# untitled.net
KiCad netlist of a schematic drawn in EAGLE
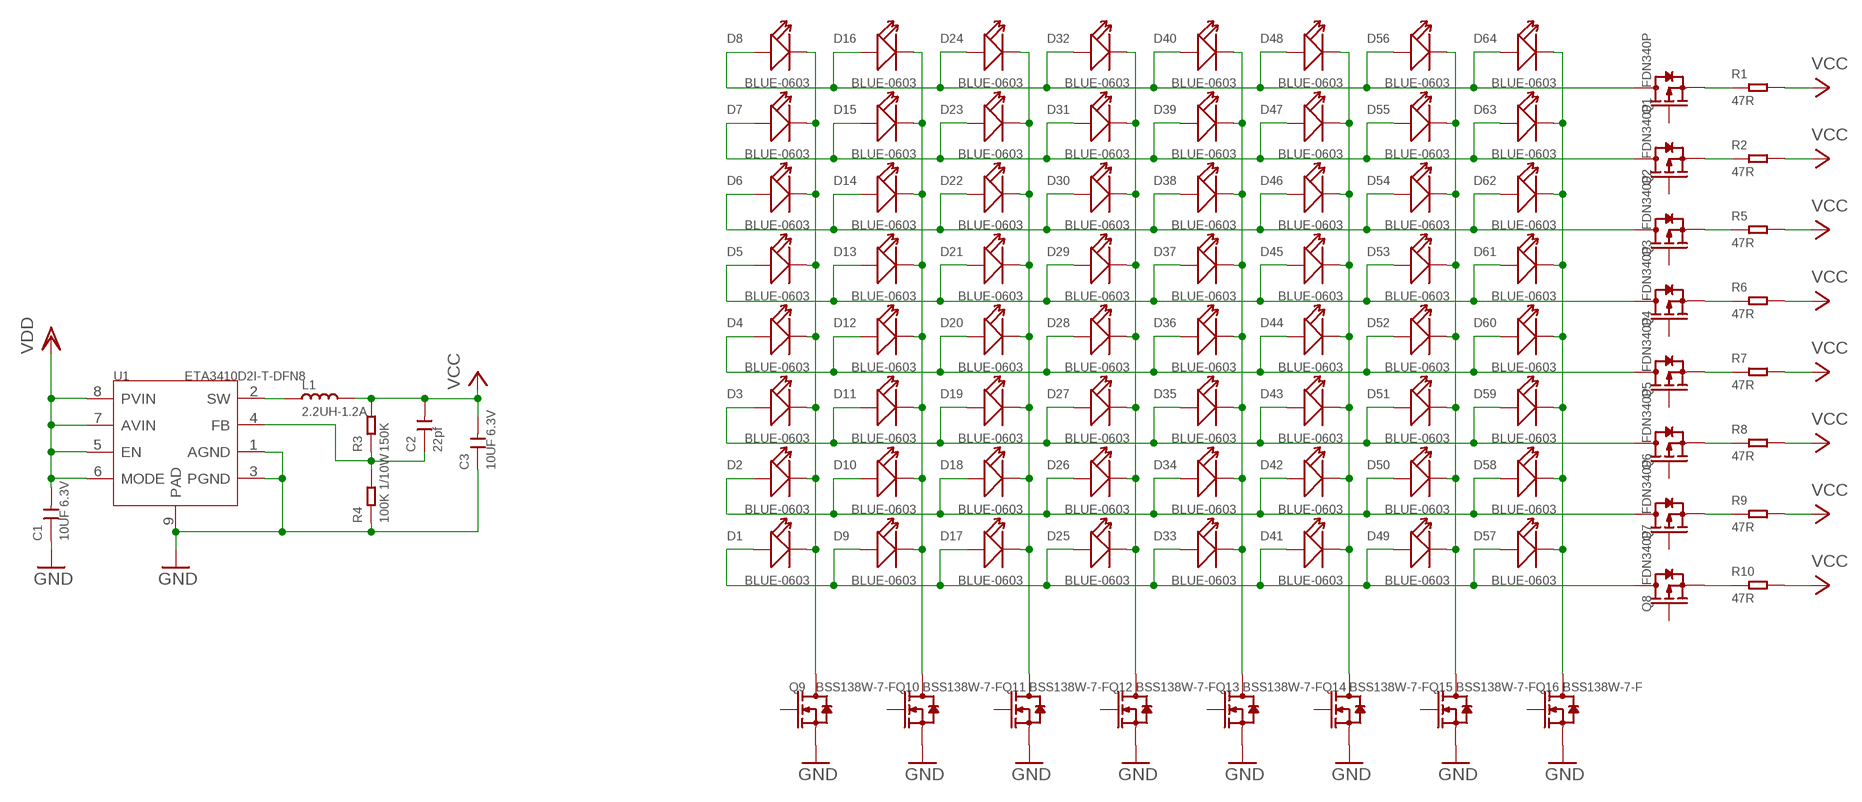
[diagram p0: schematic, sheet 1]

(export (version "E")
  (design (tool "Eeschema 10.0.6"))
  (components
    (comp (ref "C1")
      (value "10UF 6.3V")
      (footprint "eagle-import:C0603")
      (fields (field (name "MPN") "CC0603MRX5R5BB106"))
      (libsource (lib "eagle-import") (part "CERAMIC-10UF-6.3V-20%-X5R(0603)"))
    )
    (comp (ref "C2")
      (value "22pf")
      (footprint "eagle-import:C0603")
      (fields (field (name "MPN") "CC0603JRNPO9BN220"))
      (libsource (lib "eagle-import") (part "CERAMIC-22PF-50V-5%-NPO(0603)"))
    )
    (comp (ref "C3")
      (value "10UF 6.3V")
      (footprint "eagle-import:C0603")
      (fields (field (name "MPN") "CC0603MRX5R5BB106"))
      (libsource (lib "eagle-import") (part "CERAMIC-10UF-6.3V-20%-X5R(0603)"))
    )
    (comp (ref "D1")
      (value "BLUE-0603")
      (footprint "eagle-import:LED-0603")
      (fields (field (name "MPN") "19-217-BHC-ZL1M2RY-3T"))
      (libsource (lib "eagle-import") (part "SMD-LED-CLEAR-BLUE(0603)"))
    )
    (comp (ref "D2")
      (value "BLUE-0603")
      (footprint "eagle-import:LED-0603")
      (fields (field (name "MPN") "19-217-BHC-ZL1M2RY-3T"))
      (libsource (lib "eagle-import") (part "SMD-LED-CLEAR-BLUE(0603)"))
    )
    (comp (ref "D3")
      (value "BLUE-0603")
      (footprint "eagle-import:LED-0603")
      (fields (field (name "MPN") "19-217-BHC-ZL1M2RY-3T"))
      (libsource (lib "eagle-import") (part "SMD-LED-CLEAR-BLUE(0603)"))
    )
    (comp (ref "D4")
      (value "BLUE-0603")
      (footprint "eagle-import:LED-0603")
      (fields (field (name "MPN") "19-217-BHC-ZL1M2RY-3T"))
      (libsource (lib "eagle-import") (part "SMD-LED-CLEAR-BLUE(0603)"))
    )
    (comp (ref "D5")
      (value "BLUE-0603")
      (footprint "eagle-import:LED-0603")
      (fields (field (name "MPN") "19-217-BHC-ZL1M2RY-3T"))
      (libsource (lib "eagle-import") (part "SMD-LED-CLEAR-BLUE(0603)"))
    )
    (comp (ref "D6")
      (value "BLUE-0603")
      (footprint "eagle-import:LED-0603")
      (fields (field (name "MPN") "19-217-BHC-ZL1M2RY-3T"))
      (libsource (lib "eagle-import") (part "SMD-LED-CLEAR-BLUE(0603)"))
    )
    (comp (ref "D7")
      (value "BLUE-0603")
      (footprint "eagle-import:LED-0603")
      (fields (field (name "MPN") "19-217-BHC-ZL1M2RY-3T"))
      (libsource (lib "eagle-import") (part "SMD-LED-CLEAR-BLUE(0603)"))
    )
    (comp (ref "D8")
      (value "BLUE-0603")
      (footprint "eagle-import:LED-0603")
      (fields (field (name "MPN") "19-217-BHC-ZL1M2RY-3T"))
      (libsource (lib "eagle-import") (part "SMD-LED-CLEAR-BLUE(0603)"))
    )
    (comp (ref "D9")
      (value "BLUE-0603")
      (footprint "eagle-import:LED-0603")
      (fields (field (name "MPN") "19-217-BHC-ZL1M2RY-3T"))
      (libsource (lib "eagle-import") (part "SMD-LED-CLEAR-BLUE(0603)"))
    )
    (comp (ref "D10")
      (value "BLUE-0603")
      (footprint "eagle-import:LED-0603")
      (fields (field (name "MPN") "19-217-BHC-ZL1M2RY-3T"))
      (libsource (lib "eagle-import") (part "SMD-LED-CLEAR-BLUE(0603)"))
    )
    (comp (ref "D11")
      (value "BLUE-0603")
      (footprint "eagle-import:LED-0603")
      (fields (field (name "MPN") "19-217-BHC-ZL1M2RY-3T"))
      (libsource (lib "eagle-import") (part "SMD-LED-CLEAR-BLUE(0603)"))
    )
    (comp (ref "D12")
      (value "BLUE-0603")
      (footprint "eagle-import:LED-0603")
      (fields (field (name "MPN") "19-217-BHC-ZL1M2RY-3T"))
      (libsource (lib "eagle-import") (part "SMD-LED-CLEAR-BLUE(0603)"))
    )
    (comp (ref "D13")
      (value "BLUE-0603")
      (footprint "eagle-import:LED-0603")
      (fields (field (name "MPN") "19-217-BHC-ZL1M2RY-3T"))
      (libsource (lib "eagle-import") (part "SMD-LED-CLEAR-BLUE(0603)"))
    )
    (comp (ref "D14")
      (value "BLUE-0603")
      (footprint "eagle-import:LED-0603")
      (fields (field (name "MPN") "19-217-BHC-ZL1M2RY-3T"))
      (libsource (lib "eagle-import") (part "SMD-LED-CLEAR-BLUE(0603)"))
    )
    (comp (ref "D15")
      (value "BLUE-0603")
      (footprint "eagle-import:LED-0603")
      (fields (field (name "MPN") "19-217-BHC-ZL1M2RY-3T"))
      (libsource (lib "eagle-import") (part "SMD-LED-CLEAR-BLUE(0603)"))
    )
    (comp (ref "D16")
      (value "BLUE-0603")
      (footprint "eagle-import:LED-0603")
      (fields (field (name "MPN") "19-217-BHC-ZL1M2RY-3T"))
      (libsource (lib "eagle-import") (part "SMD-LED-CLEAR-BLUE(0603)"))
    )
    (comp (ref "D17")
      (value "BLUE-0603")
      (footprint "eagle-import:LED-0603")
      (fields (field (name "MPN") "19-217-BHC-ZL1M2RY-3T"))
      (libsource (lib "eagle-import") (part "SMD-LED-CLEAR-BLUE(0603)"))
    )
    (comp (ref "D18")
      (value "BLUE-0603")
      (footprint "eagle-import:LED-0603")
      (fields (field (name "MPN") "19-217-BHC-ZL1M2RY-3T"))
      (libsource (lib "eagle-import") (part "SMD-LED-CLEAR-BLUE(0603)"))
    )
    (comp (ref "D19")
      (value "BLUE-0603")
      (footprint "eagle-import:LED-0603")
      (fields (field (name "MPN") "19-217-BHC-ZL1M2RY-3T"))
      (libsource (lib "eagle-import") (part "SMD-LED-CLEAR-BLUE(0603)"))
    )
    (comp (ref "D20")
      (value "BLUE-0603")
      (footprint "eagle-import:LED-0603")
      (fields (field (name "MPN") "19-217-BHC-ZL1M2RY-3T"))
      (libsource (lib "eagle-import") (part "SMD-LED-CLEAR-BLUE(0603)"))
    )
    (comp (ref "D21")
      (value "BLUE-0603")
      (footprint "eagle-import:LED-0603")
      (fields (field (name "MPN") "19-217-BHC-ZL1M2RY-3T"))
      (libsource (lib "eagle-import") (part "SMD-LED-CLEAR-BLUE(0603)"))
    )
    (comp (ref "D22")
      (value "BLUE-0603")
      (footprint "eagle-import:LED-0603")
      (fields (field (name "MPN") "19-217-BHC-ZL1M2RY-3T"))
      (libsource (lib "eagle-import") (part "SMD-LED-CLEAR-BLUE(0603)"))
    )
    (comp (ref "D23")
      (value "BLUE-0603")
      (footprint "eagle-import:LED-0603")
      (fields (field (name "MPN") "19-217-BHC-ZL1M2RY-3T"))
      (libsource (lib "eagle-import") (part "SMD-LED-CLEAR-BLUE(0603)"))
    )
    (comp (ref "D24")
      (value "BLUE-0603")
      (footprint "eagle-import:LED-0603")
      (fields (field (name "MPN") "19-217-BHC-ZL1M2RY-3T"))
      (libsource (lib "eagle-import") (part "SMD-LED-CLEAR-BLUE(0603)"))
    )
    (comp (ref "D25")
      (value "BLUE-0603")
      (footprint "eagle-import:LED-0603")
      (fields (field (name "MPN") "19-217-BHC-ZL1M2RY-3T"))
      (libsource (lib "eagle-import") (part "SMD-LED-CLEAR-BLUE(0603)"))
    )
    (comp (ref "D26")
      (value "BLUE-0603")
      (footprint "eagle-import:LED-0603")
      (fields (field (name "MPN") "19-217-BHC-ZL1M2RY-3T"))
      (libsource (lib "eagle-import") (part "SMD-LED-CLEAR-BLUE(0603)"))
    )
    (comp (ref "D27")
      (value "BLUE-0603")
      (footprint "eagle-import:LED-0603")
      (fields (field (name "MPN") "19-217-BHC-ZL1M2RY-3T"))
      (libsource (lib "eagle-import") (part "SMD-LED-CLEAR-BLUE(0603)"))
    )
    (comp (ref "D28")
      (value "BLUE-0603")
      (footprint "eagle-import:LED-0603")
      (fields (field (name "MPN") "19-217-BHC-ZL1M2RY-3T"))
      (libsource (lib "eagle-import") (part "SMD-LED-CLEAR-BLUE(0603)"))
    )
    (comp (ref "D29")
      (value "BLUE-0603")
      (footprint "eagle-import:LED-0603")
      (fields (field (name "MPN") "19-217-BHC-ZL1M2RY-3T"))
      (libsource (lib "eagle-import") (part "SMD-LED-CLEAR-BLUE(0603)"))
    )
    (comp (ref "D30")
      (value "BLUE-0603")
      (footprint "eagle-import:LED-0603")
      (fields (field (name "MPN") "19-217-BHC-ZL1M2RY-3T"))
      (libsource (lib "eagle-import") (part "SMD-LED-CLEAR-BLUE(0603)"))
    )
    (comp (ref "D31")
      (value "BLUE-0603")
      (footprint "eagle-import:LED-0603")
      (fields (field (name "MPN") "19-217-BHC-ZL1M2RY-3T"))
      (libsource (lib "eagle-import") (part "SMD-LED-CLEAR-BLUE(0603)"))
    )
    (comp (ref "D32")
      (value "BLUE-0603")
      (footprint "eagle-import:LED-0603")
      (fields (field (name "MPN") "19-217-BHC-ZL1M2RY-3T"))
      (libsource (lib "eagle-import") (part "SMD-LED-CLEAR-BLUE(0603)"))
    )
    (comp (ref "D33")
      (value "BLUE-0603")
      (footprint "eagle-import:LED-0603")
      (fields (field (name "MPN") "19-217-BHC-ZL1M2RY-3T"))
      (libsource (lib "eagle-import") (part "SMD-LED-CLEAR-BLUE(0603)"))
    )
    (comp (ref "D34")
      (value "BLUE-0603")
      (footprint "eagle-import:LED-0603")
      (fields (field (name "MPN") "19-217-BHC-ZL1M2RY-3T"))
      (libsource (lib "eagle-import") (part "SMD-LED-CLEAR-BLUE(0603)"))
    )
    (comp (ref "D35")
      (value "BLUE-0603")
      (footprint "eagle-import:LED-0603")
      (fields (field (name "MPN") "19-217-BHC-ZL1M2RY-3T"))
      (libsource (lib "eagle-import") (part "SMD-LED-CLEAR-BLUE(0603)"))
    )
    (comp (ref "D36")
      (value "BLUE-0603")
      (footprint "eagle-import:LED-0603")
      (fields (field (name "MPN") "19-217-BHC-ZL1M2RY-3T"))
      (libsource (lib "eagle-import") (part "SMD-LED-CLEAR-BLUE(0603)"))
    )
    (comp (ref "D37")
      (value "BLUE-0603")
      (footprint "eagle-import:LED-0603")
      (fields (field (name "MPN") "19-217-BHC-ZL1M2RY-3T"))
      (libsource (lib "eagle-import") (part "SMD-LED-CLEAR-BLUE(0603)"))
    )
    (comp (ref "D38")
      (value "BLUE-0603")
      (footprint "eagle-import:LED-0603")
      (fields (field (name "MPN") "19-217-BHC-ZL1M2RY-3T"))
      (libsource (lib "eagle-import") (part "SMD-LED-CLEAR-BLUE(0603)"))
    )
    (comp (ref "D39")
      (value "BLUE-0603")
      (footprint "eagle-import:LED-0603")
      (fields (field (name "MPN") "19-217-BHC-ZL1M2RY-3T"))
      (libsource (lib "eagle-import") (part "SMD-LED-CLEAR-BLUE(0603)"))
    )
    (comp (ref "D40")
      (value "BLUE-0603")
      (footprint "eagle-import:LED-0603")
      (fields (field (name "MPN") "19-217-BHC-ZL1M2RY-3T"))
      (libsource (lib "eagle-import") (part "SMD-LED-CLEAR-BLUE(0603)"))
    )
    (comp (ref "D41")
      (value "BLUE-0603")
      (footprint "eagle-import:LED-0603")
      (fields (field (name "MPN") "19-217-BHC-ZL1M2RY-3T"))
      (libsource (lib "eagle-import") (part "SMD-LED-CLEAR-BLUE(0603)"))
    )
    (comp (ref "D42")
      (value "BLUE-0603")
      (footprint "eagle-import:LED-0603")
      (fields (field (name "MPN") "19-217-BHC-ZL1M2RY-3T"))
      (libsource (lib "eagle-import") (part "SMD-LED-CLEAR-BLUE(0603)"))
    )
    (comp (ref "D43")
      (value "BLUE-0603")
      (footprint "eagle-import:LED-0603")
      (fields (field (name "MPN") "19-217-BHC-ZL1M2RY-3T"))
      (libsource (lib "eagle-import") (part "SMD-LED-CLEAR-BLUE(0603)"))
    )
    (comp (ref "D44")
      (value "BLUE-0603")
      (footprint "eagle-import:LED-0603")
      (fields (field (name "MPN") "19-217-BHC-ZL1M2RY-3T"))
      (libsource (lib "eagle-import") (part "SMD-LED-CLEAR-BLUE(0603)"))
    )
    (comp (ref "D45")
      (value "BLUE-0603")
      (footprint "eagle-import:LED-0603")
      (fields (field (name "MPN") "19-217-BHC-ZL1M2RY-3T"))
      (libsource (lib "eagle-import") (part "SMD-LED-CLEAR-BLUE(0603)"))
    )
    (comp (ref "D46")
      (value "BLUE-0603")
      (footprint "eagle-import:LED-0603")
      (fields (field (name "MPN") "19-217-BHC-ZL1M2RY-3T"))
      (libsource (lib "eagle-import") (part "SMD-LED-CLEAR-BLUE(0603)"))
    )
    (comp (ref "D47")
      (value "BLUE-0603")
      (footprint "eagle-import:LED-0603")
      (fields (field (name "MPN") "19-217-BHC-ZL1M2RY-3T"))
      (libsource (lib "eagle-import") (part "SMD-LED-CLEAR-BLUE(0603)"))
    )
    (comp (ref "D48")
      (value "BLUE-0603")
      (footprint "eagle-import:LED-0603")
      (fields (field (name "MPN") "19-217-BHC-ZL1M2RY-3T"))
      (libsource (lib "eagle-import") (part "SMD-LED-CLEAR-BLUE(0603)"))
    )
    (comp (ref "D49")
      (value "BLUE-0603")
      (footprint "eagle-import:LED-0603")
      (fields (field (name "MPN") "19-217-BHC-ZL1M2RY-3T"))
      (libsource (lib "eagle-import") (part "SMD-LED-CLEAR-BLUE(0603)"))
    )
    (comp (ref "D50")
      (value "BLUE-0603")
      (footprint "eagle-import:LED-0603")
      (fields (field (name "MPN") "19-217-BHC-ZL1M2RY-3T"))
      (libsource (lib "eagle-import") (part "SMD-LED-CLEAR-BLUE(0603)"))
    )
    (comp (ref "D51")
      (value "BLUE-0603")
      (footprint "eagle-import:LED-0603")
      (fields (field (name "MPN") "19-217-BHC-ZL1M2RY-3T"))
      (libsource (lib "eagle-import") (part "SMD-LED-CLEAR-BLUE(0603)"))
    )
    (comp (ref "D52")
      (value "BLUE-0603")
      (footprint "eagle-import:LED-0603")
      (fields (field (name "MPN") "19-217-BHC-ZL1M2RY-3T"))
      (libsource (lib "eagle-import") (part "SMD-LED-CLEAR-BLUE(0603)"))
    )
    (comp (ref "D53")
      (value "BLUE-0603")
      (footprint "eagle-import:LED-0603")
      (fields (field (name "MPN") "19-217-BHC-ZL1M2RY-3T"))
      (libsource (lib "eagle-import") (part "SMD-LED-CLEAR-BLUE(0603)"))
    )
    (comp (ref "D54")
      (value "BLUE-0603")
      (footprint "eagle-import:LED-0603")
      (fields (field (name "MPN") "19-217-BHC-ZL1M2RY-3T"))
      (libsource (lib "eagle-import") (part "SMD-LED-CLEAR-BLUE(0603)"))
    )
    (comp (ref "D55")
      (value "BLUE-0603")
      (footprint "eagle-import:LED-0603")
      (fields (field (name "MPN") "19-217-BHC-ZL1M2RY-3T"))
      (libsource (lib "eagle-import") (part "SMD-LED-CLEAR-BLUE(0603)"))
    )
    (comp (ref "D56")
      (value "BLUE-0603")
      (footprint "eagle-import:LED-0603")
      (fields (field (name "MPN") "19-217-BHC-ZL1M2RY-3T"))
      (libsource (lib "eagle-import") (part "SMD-LED-CLEAR-BLUE(0603)"))
    )
    (comp (ref "D57")
      (value "BLUE-0603")
      (footprint "eagle-import:LED-0603")
      (fields (field (name "MPN") "19-217-BHC-ZL1M2RY-3T"))
      (libsource (lib "eagle-import") (part "SMD-LED-CLEAR-BLUE(0603)"))
    )
    (comp (ref "D58")
      (value "BLUE-0603")
      (footprint "eagle-import:LED-0603")
      (fields (field (name "MPN") "19-217-BHC-ZL1M2RY-3T"))
      (libsource (lib "eagle-import") (part "SMD-LED-CLEAR-BLUE(0603)"))
    )
    (comp (ref "D59")
      (value "BLUE-0603")
      (footprint "eagle-import:LED-0603")
      (fields (field (name "MPN") "19-217-BHC-ZL1M2RY-3T"))
      (libsource (lib "eagle-import") (part "SMD-LED-CLEAR-BLUE(0603)"))
    )
    (comp (ref "D60")
      (value "BLUE-0603")
      (footprint "eagle-import:LED-0603")
      (fields (field (name "MPN") "19-217-BHC-ZL1M2RY-3T"))
      (libsource (lib "eagle-import") (part "SMD-LED-CLEAR-BLUE(0603)"))
    )
    (comp (ref "D61")
      (value "BLUE-0603")
      (footprint "eagle-import:LED-0603")
      (fields (field (name "MPN") "19-217-BHC-ZL1M2RY-3T"))
      (libsource (lib "eagle-import") (part "SMD-LED-CLEAR-BLUE(0603)"))
    )
    (comp (ref "D62")
      (value "BLUE-0603")
      (footprint "eagle-import:LED-0603")
      (fields (field (name "MPN") "19-217-BHC-ZL1M2RY-3T"))
      (libsource (lib "eagle-import") (part "SMD-LED-CLEAR-BLUE(0603)"))
    )
    (comp (ref "D63")
      (value "BLUE-0603")
      (footprint "eagle-import:LED-0603")
      (fields (field (name "MPN") "19-217-BHC-ZL1M2RY-3T"))
      (libsource (lib "eagle-import") (part "SMD-LED-CLEAR-BLUE(0603)"))
    )
    (comp (ref "D64")
      (value "BLUE-0603")
      (footprint "eagle-import:LED-0603")
      (fields (field (name "MPN") "19-217-BHC-ZL1M2RY-3T"))
      (libsource (lib "eagle-import") (part "SMD-LED-CLEAR-BLUE(0603)"))
    )
    (comp (ref "L1")
      (value "2.2UH-1.2A")
      (footprint "eagle-import:L0805")
      (fields (field (name "MPN") "LQM2MPN2R2MG0"))
      (libsource (lib "eagle-import") (part "SMD-INDUCTOR-2.2UH-20%-1.2A(0805)"))
    )
    (comp (ref "Q1")
      (value "FDN340P")
      (footprint "eagle-import:SOT-23")
      (libsource (lib "eagle-import") (part "SMD-MOSFET-P-CH-20V-2A-FDN340P(SOT-23)"))
    )
    (comp (ref "Q2")
      (value "FDN340P")
      (footprint "eagle-import:SOT-23")
      (libsource (lib "eagle-import") (part "SMD-MOSFET-P-CH-20V-2A-FDN340P(SOT-23)"))
    )
    (comp (ref "Q3")
      (value "FDN340P")
      (footprint "eagle-import:SOT-23")
      (libsource (lib "eagle-import") (part "SMD-MOSFET-P-CH-20V-2A-FDN340P(SOT-23)"))
    )
    (comp (ref "Q4")
      (value "FDN340P")
      (footprint "eagle-import:SOT-23")
      (libsource (lib "eagle-import") (part "SMD-MOSFET-P-CH-20V-2A-FDN340P(SOT-23)"))
    )
    (comp (ref "Q5")
      (value "FDN340P")
      (footprint "eagle-import:SOT-23")
      (libsource (lib "eagle-import") (part "SMD-MOSFET-P-CH-20V-2A-FDN340P(SOT-23)"))
    )
    (comp (ref "Q6")
      (value "FDN340P")
      (footprint "eagle-import:SOT-23")
      (libsource (lib "eagle-import") (part "SMD-MOSFET-P-CH-20V-2A-FDN340P(SOT-23)"))
    )
    (comp (ref "Q7")
      (value "FDN340P")
      (footprint "eagle-import:SOT-23")
      (libsource (lib "eagle-import") (part "SMD-MOSFET-P-CH-20V-2A-FDN340P(SOT-23)"))
    )
    (comp (ref "Q8")
      (value "FDN340P")
      (footprint "eagle-import:SOT-23")
      (libsource (lib "eagle-import") (part "SMD-MOSFET-P-CH-20V-2A-FDN340P(SOT-23)"))
    )
    (comp (ref "Q9")
      (value "BSS138W-7-F")
      (footprint "eagle-import:SOT-23")
      (libsource (lib "eagle-import") (part "SMD-MOSFET-N-CH-50V-200MA-BSS138W-7-F(SOT-23)"))
    )
    (comp (ref "Q10")
      (value "BSS138W-7-F")
      (footprint "eagle-import:SOT-23")
      (libsource (lib "eagle-import") (part "SMD-MOSFET-N-CH-50V-200MA-BSS138W-7-F(SOT-23)"))
    )
    (comp (ref "Q11")
      (value "BSS138W-7-F")
      (footprint "eagle-import:SOT-23")
      (libsource (lib "eagle-import") (part "SMD-MOSFET-N-CH-50V-200MA-BSS138W-7-F(SOT-23)"))
    )
    (comp (ref "Q12")
      (value "BSS138W-7-F")
      (footprint "eagle-import:SOT-23")
      (libsource (lib "eagle-import") (part "SMD-MOSFET-N-CH-50V-200MA-BSS138W-7-F(SOT-23)"))
    )
    (comp (ref "Q13")
      (value "BSS138W-7-F")
      (footprint "eagle-import:SOT-23")
      (libsource (lib "eagle-import") (part "SMD-MOSFET-N-CH-50V-200MA-BSS138W-7-F(SOT-23)"))
    )
    (comp (ref "Q14")
      (value "BSS138W-7-F")
      (footprint "eagle-import:SOT-23")
      (libsource (lib "eagle-import") (part "SMD-MOSFET-N-CH-50V-200MA-BSS138W-7-F(SOT-23)"))
    )
    (comp (ref "Q15")
      (value "BSS138W-7-F")
      (footprint "eagle-import:SOT-23")
      (libsource (lib "eagle-import") (part "SMD-MOSFET-N-CH-50V-200MA-BSS138W-7-F(SOT-23)"))
    )
    (comp (ref "Q16")
      (value "BSS138W-7-F")
      (footprint "eagle-import:SOT-23")
      (libsource (lib "eagle-import") (part "SMD-MOSFET-N-CH-50V-200MA-BSS138W-7-F(SOT-23)"))
    )
    (comp (ref "R1")
      (value "47R")
      (footprint "eagle-import:PR-D2.3XL6.5MM")
      (fields (field (name "MPN") "FHCFR-1/4W-470J"))
      (libsource (lib "eagle-import") (part "DIP-RES-47R-5%-1/4W(PR-D2.3XL6.5MM)"))
    )
    (comp (ref "R2")
      (value "47R")
      (footprint "eagle-import:PR-D2.3XL6.5MM")
      (fields (field (name "MPN") "FHCFR-1/4W-470J"))
      (libsource (lib "eagle-import") (part "DIP-RES-47R-5%-1/4W(PR-D2.3XL6.5MM)"))
    )
    (comp (ref "R3")
      (value "150K")
      (footprint "eagle-import:R0603")
      (fields (field (name "MPN") "RC0603FR-07150KL"))
      (libsource (lib "eagle-import") (part "SMD-RES-150K-1%-1/10W(0603)"))
    )
    (comp (ref "R4")
      (value "100K 1/10W")
      (footprint "eagle-import:R0603")
      (fields (field (name "MPN") "RC0603JR-07100KL"))
      (libsource (lib "eagle-import") (part "SMD-RES-100K-5%-1/10W(0603)"))
    )
    (comp (ref "R5")
      (value "47R")
      (footprint "eagle-import:PR-D2.3XL6.5MM")
      (fields (field (name "MPN") "FHCFR-1/4W-470J"))
      (libsource (lib "eagle-import") (part "DIP-RES-47R-5%-1/4W(PR-D2.3XL6.5MM)"))
    )
    (comp (ref "R6")
      (value "47R")
      (footprint "eagle-import:PR-D2.3XL6.5MM")
      (fields (field (name "MPN") "FHCFR-1/4W-470J"))
      (libsource (lib "eagle-import") (part "DIP-RES-47R-5%-1/4W(PR-D2.3XL6.5MM)"))
    )
    (comp (ref "R7")
      (value "47R")
      (footprint "eagle-import:PR-D2.3XL6.5MM")
      (fields (field (name "MPN") "FHCFR-1/4W-470J"))
      (libsource (lib "eagle-import") (part "DIP-RES-47R-5%-1/4W(PR-D2.3XL6.5MM)"))
    )
    (comp (ref "R8")
      (value "47R")
      (footprint "eagle-import:PR-D2.3XL6.5MM")
      (fields (field (name "MPN") "FHCFR-1/4W-470J"))
      (libsource (lib "eagle-import") (part "DIP-RES-47R-5%-1/4W(PR-D2.3XL6.5MM)"))
    )
    (comp (ref "R9")
      (value "47R")
      (footprint "eagle-import:PR-D2.3XL6.5MM")
      (fields (field (name "MPN") "FHCFR-1/4W-470J"))
      (libsource (lib "eagle-import") (part "DIP-RES-47R-5%-1/4W(PR-D2.3XL6.5MM)"))
    )
    (comp (ref "R10")
      (value "47R")
      (footprint "eagle-import:PR-D2.3XL6.5MM")
      (fields (field (name "MPN") "FHCFR-1/4W-470J"))
      (libsource (lib "eagle-import") (part "DIP-RES-47R-5%-1/4W(PR-D2.3XL6.5MM)"))
    )
    (comp (ref "U1")
      (value "ETA3410D2I-T-DFN8")
      (footprint "eagle-import:DFN8G-0.5-2X2MM")
      (fields (field (name "MPN") "ETA3410D2I-T"))
      (libsource (lib "eagle-import") (part "PMIC-ETA3410D2I-T(DFN8-2X2)"))
    )
  )
  (nets
    (net (code "1") (name "GND") (class "Default")
      (node (ref "C1") (pin "1") (pinfunction "1_1") (pintype "passive"))
      (node (ref "C3") (pin "1") (pinfunction "1_1") (pintype "passive"))
      (node (ref "Q10") (pin "2") (pinfunction "S_2") (pintype "passive"))
      (node (ref "Q11") (pin "2") (pinfunction "S_2") (pintype "passive"))
      (node (ref "Q12") (pin "2") (pinfunction "S_2") (pintype "passive"))
      (node (ref "Q13") (pin "2") (pinfunction "S_2") (pintype "passive"))
      (node (ref "Q14") (pin "2") (pinfunction "S_2") (pintype "passive"))
      (node (ref "Q15") (pin "2") (pinfunction "S_2") (pintype "passive"))
      (node (ref "Q16") (pin "2") (pinfunction "S_2") (pintype "passive"))
      (node (ref "Q9") (pin "2") (pinfunction "S_2") (pintype "passive"))
      (node (ref "R4") (pin "1") (pinfunction "1_1") (pintype "passive"))
      (node (ref "U1") (pin "1") (pinfunction "AGND_1") (pintype "bidirectional"))
      (node (ref "U1") (pin "3") (pinfunction "PGND_3") (pintype "bidirectional"))
      (node (ref "U1") (pin "9") (pinfunction "PAD_9") (pintype "bidirectional"))
    )
    (net (code "2") (name "Net-(Q1-D)") (class "Default")
      (node (ref "D16") (pin "+") (pinfunction "+_+") (pintype "passive"))
      (node (ref "D24") (pin "+") (pinfunction "+_+") (pintype "passive"))
      (node (ref "D32") (pin "+") (pinfunction "+_+") (pintype "passive"))
      (node (ref "D40") (pin "+") (pinfunction "+_+") (pintype "passive"))
      (node (ref "D48") (pin "+") (pinfunction "+_+") (pintype "passive"))
      (node (ref "D56") (pin "+") (pinfunction "+_+") (pintype "passive"))
      (node (ref "D64") (pin "+") (pinfunction "+_+") (pintype "passive"))
      (node (ref "D8") (pin "+") (pinfunction "+_+") (pintype "passive"))
      (node (ref "Q1") (pin "3") (pinfunction "D_3") (pintype "passive"))
    )
    (net (code "3") (name "Net-(Q1-S)") (class "Default")
      (node (ref "Q1") (pin "2") (pinfunction "S_2") (pintype "passive"))
      (node (ref "R1") (pin "1") (pinfunction "1_1") (pintype "passive"))
    )
    (net (code "4") (name "Net-(Q2-D)") (class "Default")
      (node (ref "D15") (pin "+") (pinfunction "+_+") (pintype "passive"))
      (node (ref "D23") (pin "+") (pinfunction "+_+") (pintype "passive"))
      (node (ref "D31") (pin "+") (pinfunction "+_+") (pintype "passive"))
      (node (ref "D39") (pin "+") (pinfunction "+_+") (pintype "passive"))
      (node (ref "D47") (pin "+") (pinfunction "+_+") (pintype "passive"))
      (node (ref "D55") (pin "+") (pinfunction "+_+") (pintype "passive"))
      (node (ref "D63") (pin "+") (pinfunction "+_+") (pintype "passive"))
      (node (ref "D7") (pin "+") (pinfunction "+_+") (pintype "passive"))
      (node (ref "Q2") (pin "3") (pinfunction "D_3") (pintype "passive"))
    )
    (net (code "5") (name "Net-(Q2-S)") (class "Default")
      (node (ref "Q2") (pin "2") (pinfunction "S_2") (pintype "passive"))
      (node (ref "R2") (pin "1") (pinfunction "1_1") (pintype "passive"))
    )
    (net (code "6") (name "Net-(Q3-D)") (class "Default")
      (node (ref "D14") (pin "+") (pinfunction "+_+") (pintype "passive"))
      (node (ref "D22") (pin "+") (pinfunction "+_+") (pintype "passive"))
      (node (ref "D30") (pin "+") (pinfunction "+_+") (pintype "passive"))
      (node (ref "D38") (pin "+") (pinfunction "+_+") (pintype "passive"))
      (node (ref "D46") (pin "+") (pinfunction "+_+") (pintype "passive"))
      (node (ref "D54") (pin "+") (pinfunction "+_+") (pintype "passive"))
      (node (ref "D6") (pin "+") (pinfunction "+_+") (pintype "passive"))
      (node (ref "D62") (pin "+") (pinfunction "+_+") (pintype "passive"))
      (node (ref "Q3") (pin "3") (pinfunction "D_3") (pintype "passive"))
    )
    (net (code "7") (name "Net-(Q3-S)") (class "Default")
      (node (ref "Q3") (pin "2") (pinfunction "S_2") (pintype "passive"))
      (node (ref "R5") (pin "1") (pinfunction "1_1") (pintype "passive"))
    )
    (net (code "8") (name "Net-(Q4-D)") (class "Default")
      (node (ref "D13") (pin "+") (pinfunction "+_+") (pintype "passive"))
      (node (ref "D21") (pin "+") (pinfunction "+_+") (pintype "passive"))
      (node (ref "D29") (pin "+") (pinfunction "+_+") (pintype "passive"))
      (node (ref "D37") (pin "+") (pinfunction "+_+") (pintype "passive"))
      (node (ref "D45") (pin "+") (pinfunction "+_+") (pintype "passive"))
      (node (ref "D5") (pin "+") (pinfunction "+_+") (pintype "passive"))
      (node (ref "D53") (pin "+") (pinfunction "+_+") (pintype "passive"))
      (node (ref "D61") (pin "+") (pinfunction "+_+") (pintype "passive"))
      (node (ref "Q4") (pin "3") (pinfunction "D_3") (pintype "passive"))
    )
    (net (code "9") (name "Net-(Q4-S)") (class "Default")
      (node (ref "Q4") (pin "2") (pinfunction "S_2") (pintype "passive"))
      (node (ref "R6") (pin "1") (pinfunction "1_1") (pintype "passive"))
    )
    (net (code "10") (name "Net-(Q5-D)") (class "Default")
      (node (ref "D12") (pin "+") (pinfunction "+_+") (pintype "passive"))
      (node (ref "D20") (pin "+") (pinfunction "+_+") (pintype "passive"))
      (node (ref "D28") (pin "+") (pinfunction "+_+") (pintype "passive"))
      (node (ref "D36") (pin "+") (pinfunction "+_+") (pintype "passive"))
      (node (ref "D4") (pin "+") (pinfunction "+_+") (pintype "passive"))
      (node (ref "D44") (pin "+") (pinfunction "+_+") (pintype "passive"))
      (node (ref "D52") (pin "+") (pinfunction "+_+") (pintype "passive"))
      (node (ref "D60") (pin "+") (pinfunction "+_+") (pintype "passive"))
      (node (ref "Q5") (pin "3") (pinfunction "D_3") (pintype "passive"))
    )
    (net (code "11") (name "Net-(Q5-S)") (class "Default")
      (node (ref "Q5") (pin "2") (pinfunction "S_2") (pintype "passive"))
      (node (ref "R7") (pin "1") (pinfunction "1_1") (pintype "passive"))
    )
    (net (code "12") (name "Net-(Q6-D)") (class "Default")
      (node (ref "D11") (pin "+") (pinfunction "+_+") (pintype "passive"))
      (node (ref "D19") (pin "+") (pinfunction "+_+") (pintype "passive"))
      (node (ref "D27") (pin "+") (pinfunction "+_+") (pintype "passive"))
      (node (ref "D3") (pin "+") (pinfunction "+_+") (pintype "passive"))
      (node (ref "D35") (pin "+") (pinfunction "+_+") (pintype "passive"))
      (node (ref "D43") (pin "+") (pinfunction "+_+") (pintype "passive"))
      (node (ref "D51") (pin "+") (pinfunction "+_+") (pintype "passive"))
      (node (ref "D59") (pin "+") (pinfunction "+_+") (pintype "passive"))
      (node (ref "Q6") (pin "3") (pinfunction "D_3") (pintype "passive"))
    )
    (net (code "13") (name "Net-(Q6-S)") (class "Default")
      (node (ref "Q6") (pin "2") (pinfunction "S_2") (pintype "passive"))
      (node (ref "R8") (pin "1") (pinfunction "1_1") (pintype "passive"))
    )
    (net (code "14") (name "Net-(Q7-D)") (class "Default")
      (node (ref "D10") (pin "+") (pinfunction "+_+") (pintype "passive"))
      (node (ref "D18") (pin "+") (pinfunction "+_+") (pintype "passive"))
      (node (ref "D2") (pin "+") (pinfunction "+_+") (pintype "passive"))
      (node (ref "D26") (pin "+") (pinfunction "+_+") (pintype "passive"))
      (node (ref "D34") (pin "+") (pinfunction "+_+") (pintype "passive"))
      (node (ref "D42") (pin "+") (pinfunction "+_+") (pintype "passive"))
      (node (ref "D50") (pin "+") (pinfunction "+_+") (pintype "passive"))
      (node (ref "D58") (pin "+") (pinfunction "+_+") (pintype "passive"))
      (node (ref "Q7") (pin "3") (pinfunction "D_3") (pintype "passive"))
    )
    (net (code "15") (name "Net-(Q7-S)") (class "Default")
      (node (ref "Q7") (pin "2") (pinfunction "S_2") (pintype "passive"))
      (node (ref "R9") (pin "1") (pinfunction "1_1") (pintype "passive"))
    )
    (net (code "16") (name "Net-(Q8-D)") (class "Default")
      (node (ref "D1") (pin "+") (pinfunction "+_+") (pintype "passive"))
      (node (ref "D17") (pin "+") (pinfunction "+_+") (pintype "passive"))
      (node (ref "D25") (pin "+") (pinfunction "+_+") (pintype "passive"))
      (node (ref "D33") (pin "+") (pinfunction "+_+") (pintype "passive"))
      (node (ref "D41") (pin "+") (pinfunction "+_+") (pintype "passive"))
      (node (ref "D49") (pin "+") (pinfunction "+_+") (pintype "passive"))
      (node (ref "D57") (pin "+") (pinfunction "+_+") (pintype "passive"))
      (node (ref "D9") (pin "+") (pinfunction "+_+") (pintype "passive"))
      (node (ref "Q8") (pin "3") (pinfunction "D_3") (pintype "passive"))
    )
    (net (code "17") (name "Net-(Q8-S)") (class "Default")
      (node (ref "Q8") (pin "2") (pinfunction "S_2") (pintype "passive"))
      (node (ref "R10") (pin "1") (pinfunction "1_1") (pintype "passive"))
    )
    (net (code "18") (name "Net-(Q9-D)") (class "Default")
      (node (ref "D1") (pin "-") (pinfunction "-_-") (pintype "passive"))
      (node (ref "D2") (pin "-") (pinfunction "-_-") (pintype "passive"))
      (node (ref "D3") (pin "-") (pinfunction "-_-") (pintype "passive"))
      (node (ref "D4") (pin "-") (pinfunction "-_-") (pintype "passive"))
      (node (ref "D5") (pin "-") (pinfunction "-_-") (pintype "passive"))
      (node (ref "D6") (pin "-") (pinfunction "-_-") (pintype "passive"))
      (node (ref "D7") (pin "-") (pinfunction "-_-") (pintype "passive"))
      (node (ref "D8") (pin "-") (pinfunction "-_-") (pintype "passive"))
      (node (ref "Q9") (pin "3") (pinfunction "D_3") (pintype "passive"))
    )
    (net (code "19") (name "Net-(Q10-D)") (class "Default")
      (node (ref "D10") (pin "-") (pinfunction "-_-") (pintype "passive"))
      (node (ref "D11") (pin "-") (pinfunction "-_-") (pintype "passive"))
      (node (ref "D12") (pin "-") (pinfunction "-_-") (pintype "passive"))
      (node (ref "D13") (pin "-") (pinfunction "-_-") (pintype "passive"))
      (node (ref "D14") (pin "-") (pinfunction "-_-") (pintype "passive"))
      (node (ref "D15") (pin "-") (pinfunction "-_-") (pintype "passive"))
      (node (ref "D16") (pin "-") (pinfunction "-_-") (pintype "passive"))
      (node (ref "D9") (pin "-") (pinfunction "-_-") (pintype "passive"))
      (node (ref "Q10") (pin "3") (pinfunction "D_3") (pintype "passive"))
    )
    (net (code "20") (name "Net-(Q11-D)") (class "Default")
      (node (ref "D17") (pin "-") (pinfunction "-_-") (pintype "passive"))
      (node (ref "D18") (pin "-") (pinfunction "-_-") (pintype "passive"))
      (node (ref "D19") (pin "-") (pinfunction "-_-") (pintype "passive"))
      (node (ref "D20") (pin "-") (pinfunction "-_-") (pintype "passive"))
      (node (ref "D21") (pin "-") (pinfunction "-_-") (pintype "passive"))
      (node (ref "D22") (pin "-") (pinfunction "-_-") (pintype "passive"))
      (node (ref "D23") (pin "-") (pinfunction "-_-") (pintype "passive"))
      (node (ref "D24") (pin "-") (pinfunction "-_-") (pintype "passive"))
      (node (ref "Q11") (pin "3") (pinfunction "D_3") (pintype "passive"))
    )
    (net (code "21") (name "Net-(Q12-D)") (class "Default")
      (node (ref "D25") (pin "-") (pinfunction "-_-") (pintype "passive"))
      (node (ref "D26") (pin "-") (pinfunction "-_-") (pintype "passive"))
      (node (ref "D27") (pin "-") (pinfunction "-_-") (pintype "passive"))
      (node (ref "D28") (pin "-") (pinfunction "-_-") (pintype "passive"))
      (node (ref "D29") (pin "-") (pinfunction "-_-") (pintype "passive"))
      (node (ref "D30") (pin "-") (pinfunction "-_-") (pintype "passive"))
      (node (ref "D31") (pin "-") (pinfunction "-_-") (pintype "passive"))
      (node (ref "D32") (pin "-") (pinfunction "-_-") (pintype "passive"))
      (node (ref "Q12") (pin "3") (pinfunction "D_3") (pintype "passive"))
    )
    (net (code "22") (name "Net-(Q13-D)") (class "Default")
      (node (ref "D33") (pin "-") (pinfunction "-_-") (pintype "passive"))
      (node (ref "D34") (pin "-") (pinfunction "-_-") (pintype "passive"))
      (node (ref "D35") (pin "-") (pinfunction "-_-") (pintype "passive"))
      (node (ref "D36") (pin "-") (pinfunction "-_-") (pintype "passive"))
      (node (ref "D37") (pin "-") (pinfunction "-_-") (pintype "passive"))
      (node (ref "D38") (pin "-") (pinfunction "-_-") (pintype "passive"))
      (node (ref "D39") (pin "-") (pinfunction "-_-") (pintype "passive"))
      (node (ref "D40") (pin "-") (pinfunction "-_-") (pintype "passive"))
      (node (ref "Q13") (pin "3") (pinfunction "D_3") (pintype "passive"))
    )
    (net (code "23") (name "Net-(Q14-D)") (class "Default")
      (node (ref "D41") (pin "-") (pinfunction "-_-") (pintype "passive"))
      (node (ref "D42") (pin "-") (pinfunction "-_-") (pintype "passive"))
      (node (ref "D43") (pin "-") (pinfunction "-_-") (pintype "passive"))
      (node (ref "D44") (pin "-") (pinfunction "-_-") (pintype "passive"))
      (node (ref "D45") (pin "-") (pinfunction "-_-") (pintype "passive"))
      (node (ref "D46") (pin "-") (pinfunction "-_-") (pintype "passive"))
      (node (ref "D47") (pin "-") (pinfunction "-_-") (pintype "passive"))
      (node (ref "D48") (pin "-") (pinfunction "-_-") (pintype "passive"))
      (node (ref "Q14") (pin "3") (pinfunction "D_3") (pintype "passive"))
    )
    (net (code "24") (name "Net-(Q15-D)") (class "Default")
      (node (ref "D49") (pin "-") (pinfunction "-_-") (pintype "passive"))
      (node (ref "D50") (pin "-") (pinfunction "-_-") (pintype "passive"))
      (node (ref "D51") (pin "-") (pinfunction "-_-") (pintype "passive"))
      (node (ref "D52") (pin "-") (pinfunction "-_-") (pintype "passive"))
      (node (ref "D53") (pin "-") (pinfunction "-_-") (pintype "passive"))
      (node (ref "D54") (pin "-") (pinfunction "-_-") (pintype "passive"))
      (node (ref "D55") (pin "-") (pinfunction "-_-") (pintype "passive"))
      (node (ref "D56") (pin "-") (pinfunction "-_-") (pintype "passive"))
      (node (ref "Q15") (pin "3") (pinfunction "D_3") (pintype "passive"))
    )
    (net (code "25") (name "Net-(Q16-D)") (class "Default")
      (node (ref "D57") (pin "-") (pinfunction "-_-") (pintype "passive"))
      (node (ref "D58") (pin "-") (pinfunction "-_-") (pintype "passive"))
      (node (ref "D59") (pin "-") (pinfunction "-_-") (pintype "passive"))
      (node (ref "D60") (pin "-") (pinfunction "-_-") (pintype "passive"))
      (node (ref "D61") (pin "-") (pinfunction "-_-") (pintype "passive"))
      (node (ref "D62") (pin "-") (pinfunction "-_-") (pintype "passive"))
      (node (ref "D63") (pin "-") (pinfunction "-_-") (pintype "passive"))
      (node (ref "D64") (pin "-") (pinfunction "-_-") (pintype "passive"))
      (node (ref "Q16") (pin "3") (pinfunction "D_3") (pintype "passive"))
    )
    (net (code "26") (name "Net-(U1-FB)") (class "Default")
      (node (ref "C2") (pin "1") (pinfunction "1_1") (pintype "passive"))
      (node (ref "R3") (pin "1") (pinfunction "1_1") (pintype "passive"))
      (node (ref "R4") (pin "2") (pinfunction "2_2") (pintype "passive"))
      (node (ref "U1") (pin "4") (pinfunction "FB_4") (pintype "bidirectional"))
    )
    (net (code "27") (name "Net-(U1-SW)") (class "Default")
      (node (ref "L1") (pin "1") (pinfunction "1_1") (pintype "passive"))
      (node (ref "U1") (pin "2") (pinfunction "SW_2") (pintype "bidirectional"))
    )
    (net (code "28") (name "VCC") (class "Default")
      (node (ref "C2") (pin "2") (pinfunction "2_2") (pintype "passive"))
      (node (ref "C3") (pin "2") (pinfunction "2_2") (pintype "passive"))
      (node (ref "L1") (pin "2") (pinfunction "2_2") (pintype "passive"))
      (node (ref "R1") (pin "2") (pinfunction "2_2") (pintype "passive"))
      (node (ref "R10") (pin "2") (pinfunction "2_2") (pintype "passive"))
      (node (ref "R2") (pin "2") (pinfunction "2_2") (pintype "passive"))
      (node (ref "R3") (pin "2") (pinfunction "2_2") (pintype "passive"))
      (node (ref "R5") (pin "2") (pinfunction "2_2") (pintype "passive"))
      (node (ref "R6") (pin "2") (pinfunction "2_2") (pintype "passive"))
      (node (ref "R7") (pin "2") (pinfunction "2_2") (pintype "passive"))
      (node (ref "R8") (pin "2") (pinfunction "2_2") (pintype "passive"))
      (node (ref "R9") (pin "2") (pinfunction "2_2") (pintype "passive"))
    )
    (net (code "29") (name "VDD") (class "Default")
      (node (ref "C1") (pin "2") (pinfunction "2_2") (pintype "passive"))
      (node (ref "U1") (pin "5") (pinfunction "EN_5") (pintype "bidirectional"))
      (node (ref "U1") (pin "6") (pinfunction "MODE_6") (pintype "bidirectional"))
      (node (ref "U1") (pin "7") (pinfunction "AVIN_7") (pintype "bidirectional"))
      (node (ref "U1") (pin "8") (pinfunction "PVIN_8") (pintype "bidirectional"))
    )
    (net (code "30") (name "unconnected-(Q1-G-Pad1)") (class "Default")
      (node (ref "Q1") (pin "1") (pinfunction "G_1") (pintype "passive"))
    )
    (net (code "31") (name "unconnected-(Q2-G-Pad1)") (class "Default")
      (node (ref "Q2") (pin "1") (pinfunction "G_1") (pintype "passive"))
    )
    (net (code "32") (name "unconnected-(Q3-G-Pad1)") (class "Default")
      (node (ref "Q3") (pin "1") (pinfunction "G_1") (pintype "passive"))
    )
    (net (code "33") (name "unconnected-(Q4-G-Pad1)") (class "Default")
      (node (ref "Q4") (pin "1") (pinfunction "G_1") (pintype "passive"))
    )
    (net (code "34") (name "unconnected-(Q5-G-Pad1)") (class "Default")
      (node (ref "Q5") (pin "1") (pinfunction "G_1") (pintype "passive"))
    )
    (net (code "35") (name "unconnected-(Q6-G-Pad1)") (class "Default")
      (node (ref "Q6") (pin "1") (pinfunction "G_1") (pintype "passive"))
    )
    (net (code "36") (name "unconnected-(Q7-G-Pad1)") (class "Default")
      (node (ref "Q7") (pin "1") (pinfunction "G_1") (pintype "passive"))
    )
    (net (code "37") (name "unconnected-(Q8-G-Pad1)") (class "Default")
      (node (ref "Q8") (pin "1") (pinfunction "G_1") (pintype "passive"))
    )
    (net (code "38") (name "unconnected-(Q9-G-Pad1)") (class "Default")
      (node (ref "Q9") (pin "1") (pinfunction "G_1") (pintype "passive"))
    )
    (net (code "39") (name "unconnected-(Q10-G-Pad1)") (class "Default")
      (node (ref "Q10") (pin "1") (pinfunction "G_1") (pintype "passive"))
    )
    (net (code "40") (name "unconnected-(Q11-G-Pad1)") (class "Default")
      (node (ref "Q11") (pin "1") (pinfunction "G_1") (pintype "passive"))
    )
    (net (code "41") (name "unconnected-(Q12-G-Pad1)") (class "Default")
      (node (ref "Q12") (pin "1") (pinfunction "G_1") (pintype "passive"))
    )
    (net (code "42") (name "unconnected-(Q13-G-Pad1)") (class "Default")
      (node (ref "Q13") (pin "1") (pinfunction "G_1") (pintype "passive"))
    )
    (net (code "43") (name "unconnected-(Q14-G-Pad1)") (class "Default")
      (node (ref "Q14") (pin "1") (pinfunction "G_1") (pintype "passive"))
    )
    (net (code "44") (name "unconnected-(Q15-G-Pad1)") (class "Default")
      (node (ref "Q15") (pin "1") (pinfunction "G_1") (pintype "passive"))
    )
    (net (code "45") (name "unconnected-(Q16-G-Pad1)") (class "Default")
      (node (ref "Q16") (pin "1") (pinfunction "G_1") (pintype "passive"))
    )
  )
)
